# BMS_AFE_-_Thermistors.net
KiCad netlist of a schematic drawn in Altium Designer
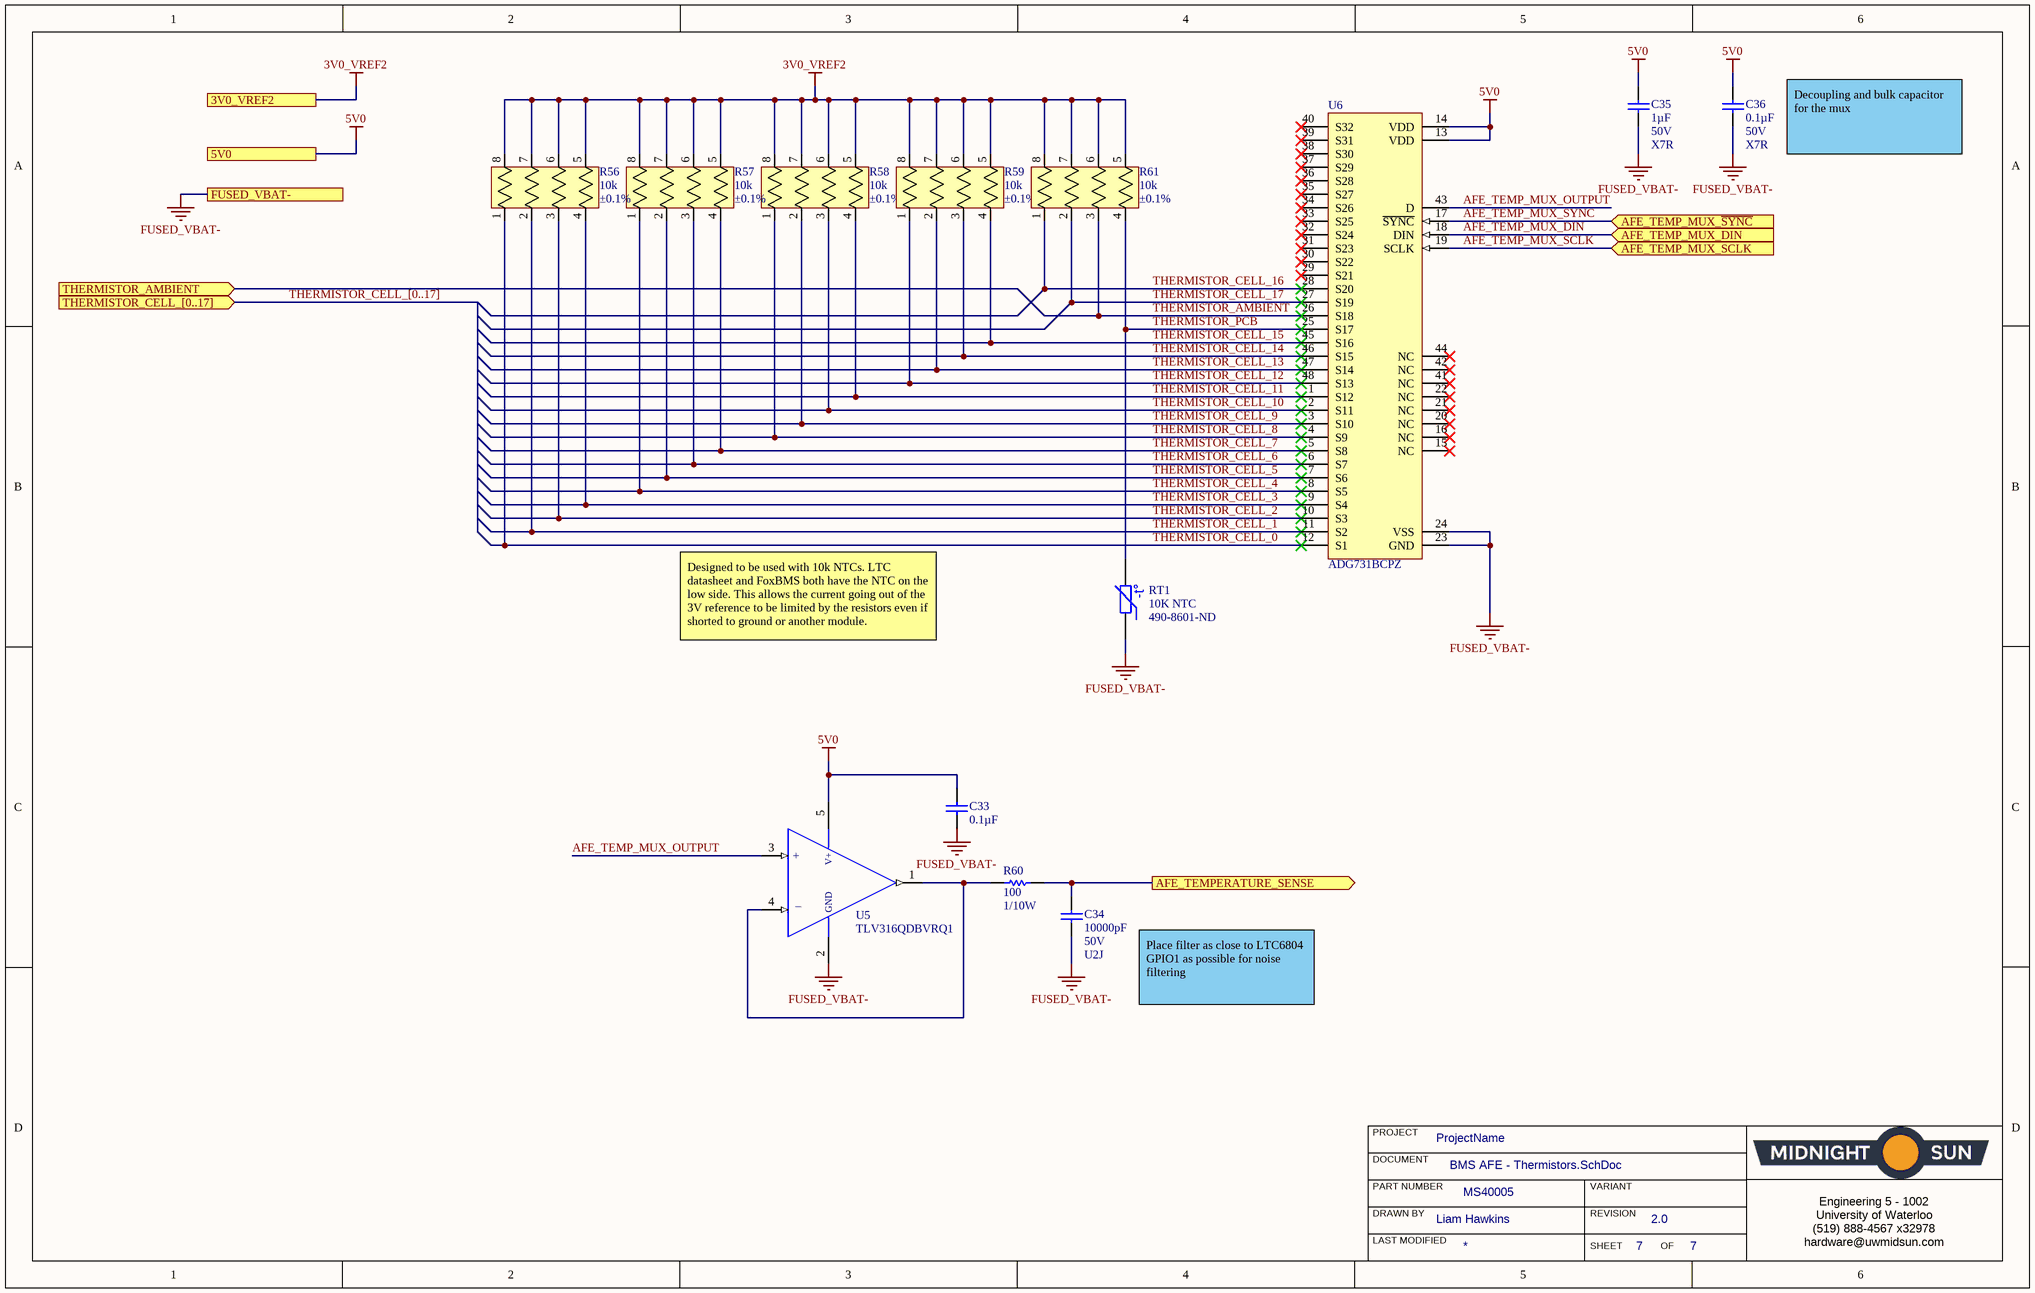
[diagram p0: BMS AFE - Thermistors.SchDoc]

(export (version "E")
  (design (tool "Eeschema 10.0.6"))
  (components
    (comp (ref "C33")
      (value "CAP CER 0.1UF 50V 10% X7R 0603")
      (footprint "CAP, 0603")
      (description "0.10µF ±10% 50V Ceramic Capacitor X7R 0603 (1608 Metric)")
      (fields
        (field (name "TOLERANCE") "±10%")
        (field (name "CAPACITANCE") "0.1µF")
        (field (name "VOLTAGE") "50V")
      )
      (libsource (lib "Schematic Diagrams") (part "CAP CER 0.1UF 50V 10% X7R 0603"))
    )
    (comp (ref "C34")
      (value "CAP CER 10nF 50V 5% X7R 0603")
      (footprint "CAP, 0603")
      (description "10000pF ±5% 50V Ceramic Capacitor U2J 0603 (1608 Metric)")
      (fields
        (field (name "TOLERANCE") "±5%")
        (field (name "CAPACITANCE") "10000pF")
        (field (name "VOLTAGE") "50V")
        (field (name "TEMPERATURE COEFFICIENT") "U2J")
      )
      (libsource (lib "Schematic Diagrams") (part "CAP CER 10nF 50V 5% X7R 0603"))
    )
    (comp (ref "C35")
      (value "CAP CER 1UF 50V 10% X7R 0603")
      (footprint "CAP, 0603")
      (description "1µF ±10% 50V Ceramic Capacitor X7R 0603 (1608 Metric)")
      (fields
        (field (name "TOLERANCE") "±10%")
        (field (name "CAPACITANCE") "1µF")
        (field (name "VOLTAGE") "50V")
        (field (name "TEMPERATURE COEFFICIENT") "X7R")
      )
      (libsource (lib "Schematic Diagrams") (part "CAP CER 1UF 50V 10% X7R 0603"))
    )
    (comp (ref "C36")
      (value "CAP CER 0.1UF 50V 10% X7R 0603")
      (footprint "CAP, 0603")
      (description "0.10µF ±10% 50V Ceramic Capacitor X7R 0603 (1608 Metric)")
      (fields
        (field (name "TOLERANCE") "±10%")
        (field (name "CAPACITANCE") "0.1µF")
        (field (name "VOLTAGE") "50V")
        (field (name "TEMPERATURE COEFFICIENT") "X7R")
      )
      (libsource (lib "Schematic Diagrams") (part "CAP CER 0.1UF 50V 10% X7R 0603"))
    )
    (comp (ref "R56")
      (value "RES ARRAY 10K OHM 0.1% 4RES 1206")
      (footprint "RES ARRAY 4RES 1206")
      (fields
        (field (name "MANUFACTURER") "Vishay Beyschlag")
        (field (name "MANUFACTURER PART NUMBER") "ACASA1002S1002P100")
        (field (name "RESISTANCE (OHMS)") "10k")
        (field (name "TOLERANCE") "±0.1%")
      )
      (libsource (lib "Schematic Diagrams") (part "RES ARRAY 10K OHM 0.1% 4RES 1206"))
    )
    (comp (ref "R57")
      (value "RES ARRAY 10K OHM 0.1% 4RES 1206")
      (footprint "RES ARRAY 4RES 1206")
      (fields
        (field (name "MANUFACTURER") "Vishay Beyschlag")
        (field (name "MANUFACTURER PART NUMBER") "ACASA1002S1002P100")
        (field (name "RESISTANCE (OHMS)") "10k")
        (field (name "TOLERANCE") "±0.1%")
      )
      (libsource (lib "Schematic Diagrams") (part "RES ARRAY 10K OHM 0.1% 4RES 1206"))
    )
    (comp (ref "R58")
      (value "RES ARRAY 10K OHM 0.1% 4RES 1206")
      (footprint "RES ARRAY 4RES 1206")
      (fields
        (field (name "MANUFACTURER") "Vishay Beyschlag")
        (field (name "MANUFACTURER PART NUMBER") "ACASA1002S1002P100")
        (field (name "RESISTANCE (OHMS)") "10k")
        (field (name "TOLERANCE") "±0.1%")
      )
      (libsource (lib "Schematic Diagrams") (part "RES ARRAY 10K OHM 0.1% 4RES 1206"))
    )
    (comp (ref "R59")
      (value "RES ARRAY 10K OHM 0.1% 4RES 1206")
      (footprint "RES ARRAY 4RES 1206")
      (fields
        (field (name "MANUFACTURER") "Vishay Beyschlag")
        (field (name "MANUFACTURER PART NUMBER") "ACASA1002S1002P100")
        (field (name "RESISTANCE (OHMS)") "10k")
        (field (name "TOLERANCE") "±0.1%")
      )
      (libsource (lib "Schematic Diagrams") (part "RES ARRAY 10K OHM 0.1% 4RES 1206"))
    )
    (comp (ref "R60")
      (value "RES 100 OHM 1% 1/10W 0603")
      (footprint "RES, 0603")
      (description "100 Ohm ±1% 0.1W, 1/10W Chip Resistor 0603 (1608 Metric) Moisture Resistant Thick Film")
      (fields
        (field (name "TOLERANCE") "±1%")
        (field (name "RESISTANCE") "100")
        (field (name "POWER") "1/10W")
      )
      (libsource (lib "Schematic Diagrams") (part "RES 100 OHM 1% 1/10W 0603"))
    )
    (comp (ref "R61")
      (value "RES ARRAY 10K OHM 0.1% 4RES 1206")
      (footprint "RES ARRAY 4RES 1206")
      (fields
        (field (name "MANUFACTURER") "Vishay Beyschlag")
        (field (name "MANUFACTURER PART NUMBER") "ACASA1002S1002P100")
        (field (name "RESISTANCE (OHMS)") "10k")
        (field (name "TOLERANCE") "±0.1%")
      )
      (libsource (lib "Schematic Diagrams") (part "RES ARRAY 10K OHM 0.1% 4RES 1206"))
    )
    (comp (ref "RT1")
      (value "10K NTC")
      (footprint "NTC THERMISTOR BEAD")
      (description "NTC Thermistor 10k Bead")
      (fields
        (field (name "MANUFACTURER") "Murata Electronics North America")
        (field (name "MANUFACTURER PART NUMBER") "NXRT15XH103FA1B030")
        (field (name "SUPPLIER PART NUMBER 1") "490-8601-ND")
      )
      (libsource (lib "Schematic Diagrams") (part "NTC THERMISTOR 10K 1% BEAD"))
    )
    (comp (ref "U5")
      (value "IC OP AMP GEN PURPOSE RR 10MHZ SOT-23-5")
      (footprint "IC OP AMP GP RR 10MHZ SOT-23-5")
      (description "General Purpose Amplifier 1 Circuit Rail-to-Rail SOT-23-5")
      (fields (field (name "MANUFACTURER PART NUMBER 1") "TLV316QDBVRQ1"))
      (libsource (lib "Schematic Diagrams") (part "IC OP AMP GEN PURPOSE RR 10MHZ SOT-23-5"))
    )
    (comp (ref "U6")
      (value "ADG731BCPZ")
      (footprint "TSQFP50P890X890X160-48M")
      (description "IC MULTIPLEXER 32X1 48LFCSP")
      (fields
        (field (name "MANUFACTURER") "Analog Devices Inc.")
        (field (name "MANUFACTURER PART NUMBER") "ADG731BSUZ")
      )
      (libsource (lib "Schematic Diagrams") (part "IC 32x1 Multiplexer ADG731BCPZ"))
    )
  )
  (nets
    (net (code "1") (name "/AFE_TEMPERATURE_SENSE") (class "Default")
      (node (ref "C34") (pin "1") (pinfunction "1_1") (pintype "passive"))
      (node (ref "R60") (pin "2") (pinfunction "2_2") (pintype "passive"))
    )
    (net (code "2") (name "/AFE_TEMP_MUX_DIN") (class "Default")
      (node (ref "U6") (pin "18") (pinfunction "DIN_18") (pintype "input"))
    )
    (net (code "3") (name "/AFE_TEMP_MUX_OUTPUT") (class "Default")
      (node (ref "U5") (pin "3") (pinfunction "+IN_3") (pintype "input"))
      (node (ref "U6") (pin "43") (pinfunction "D_43") (pintype "passive"))
    )
    (net (code "4") (name "/AFE_TEMP_MUX_SCLK") (class "Default")
      (node (ref "U6") (pin "19") (pinfunction "SCLK_19") (pintype "input"))
    )
    (net (code "5") (name "/AFE_TEMP_MUX_~{SYNC}") (class "Default")
      (node (ref "U6") (pin "17") (pinfunction "~{SYNC}_17") (pintype "input"))
    )
    (net (code "6") (name "/THERMISTOR_AMBIENT") (class "Default")
      (node (ref "R61") (pin "3") (pinfunction "3_3") (pintype "passive"))
      (node (ref "U6") (pin "26") (pinfunction "S18_26") (pintype "passive"))
    )
    (net (code "7") (name "/THERMISTOR_CELL_0") (class "Default")
      (node (ref "R56") (pin "1") (pinfunction "1_1") (pintype "passive"))
      (node (ref "U6") (pin "12") (pinfunction "S1_12") (pintype "passive"))
    )
    (net (code "8") (name "/THERMISTOR_CELL_1") (class "Default")
      (node (ref "R56") (pin "2") (pinfunction "2_2") (pintype "passive"))
      (node (ref "U6") (pin "11") (pinfunction "S2_11") (pintype "passive"))
    )
    (net (code "9") (name "/THERMISTOR_CELL_2") (class "Default")
      (node (ref "R56") (pin "3") (pinfunction "3_3") (pintype "passive"))
      (node (ref "U6") (pin "10") (pinfunction "S3_10") (pintype "passive"))
    )
    (net (code "10") (name "/THERMISTOR_CELL_3") (class "Default")
      (node (ref "R56") (pin "4") (pinfunction "4_4") (pintype "passive"))
      (node (ref "U6") (pin "9") (pinfunction "S4_9") (pintype "passive"))
    )
    (net (code "11") (name "/THERMISTOR_CELL_4") (class "Default")
      (node (ref "R57") (pin "1") (pinfunction "1_1") (pintype "passive"))
      (node (ref "U6") (pin "8") (pinfunction "S5_8") (pintype "passive"))
    )
    (net (code "12") (name "/THERMISTOR_CELL_5") (class "Default")
      (node (ref "R57") (pin "2") (pinfunction "2_2") (pintype "passive"))
      (node (ref "U6") (pin "7") (pinfunction "S6_7") (pintype "passive"))
    )
    (net (code "13") (name "/THERMISTOR_CELL_6") (class "Default")
      (node (ref "R57") (pin "3") (pinfunction "3_3") (pintype "passive"))
      (node (ref "U6") (pin "6") (pinfunction "S7_6") (pintype "passive"))
    )
    (net (code "14") (name "/THERMISTOR_CELL_7") (class "Default")
      (node (ref "R57") (pin "4") (pinfunction "4_4") (pintype "passive"))
      (node (ref "U6") (pin "5") (pinfunction "S8_5") (pintype "passive"))
    )
    (net (code "15") (name "/THERMISTOR_CELL_8") (class "Default")
      (node (ref "R58") (pin "1") (pinfunction "1_1") (pintype "passive"))
      (node (ref "U6") (pin "4") (pinfunction "S9_4") (pintype "passive"))
    )
    (net (code "16") (name "/THERMISTOR_CELL_9") (class "Default")
      (node (ref "R58") (pin "2") (pinfunction "2_2") (pintype "passive"))
      (node (ref "U6") (pin "3") (pinfunction "S10_3") (pintype "passive"))
    )
    (net (code "17") (name "/THERMISTOR_CELL_10") (class "Default")
      (node (ref "R58") (pin "3") (pinfunction "3_3") (pintype "passive"))
      (node (ref "U6") (pin "2") (pinfunction "S11_2") (pintype "passive"))
    )
    (net (code "18") (name "/THERMISTOR_CELL_11") (class "Default")
      (node (ref "R58") (pin "4") (pinfunction "4_4") (pintype "passive"))
      (node (ref "U6") (pin "1") (pinfunction "S12_1") (pintype "passive"))
    )
    (net (code "19") (name "/THERMISTOR_CELL_12") (class "Default")
      (node (ref "R59") (pin "1") (pinfunction "1_1") (pintype "passive"))
      (node (ref "U6") (pin "48") (pinfunction "S13_48") (pintype "passive"))
    )
    (net (code "20") (name "/THERMISTOR_CELL_13") (class "Default")
      (node (ref "R59") (pin "2") (pinfunction "2_2") (pintype "passive"))
      (node (ref "U6") (pin "47") (pinfunction "S14_47") (pintype "passive"))
    )
    (net (code "21") (name "/THERMISTOR_CELL_14") (class "Default")
      (node (ref "R59") (pin "3") (pinfunction "3_3") (pintype "passive"))
      (node (ref "U6") (pin "46") (pinfunction "S15_46") (pintype "passive"))
    )
    (net (code "22") (name "/THERMISTOR_CELL_15") (class "Default")
      (node (ref "R59") (pin "4") (pinfunction "4_4") (pintype "passive"))
      (node (ref "U6") (pin "45") (pinfunction "S16_45") (pintype "passive"))
    )
    (net (code "23") (name "/THERMISTOR_CELL_16") (class "Default")
      (node (ref "R61") (pin "1") (pinfunction "1_1") (pintype "passive"))
      (node (ref "U6") (pin "28") (pinfunction "S20_28") (pintype "passive"))
    )
    (net (code "24") (name "/THERMISTOR_CELL_17") (class "Default")
      (node (ref "R61") (pin "2") (pinfunction "2_2") (pintype "passive"))
      (node (ref "U6") (pin "27") (pinfunction "S19_27") (pintype "passive"))
    )
    (net (code "26") (name "/THERMISTOR_PCB") (class "Default")
      (node (ref "R61") (pin "4") (pinfunction "4_4") (pintype "passive"))
      (node (ref "RT1") (pin "2") (pinfunction "2_2") (pintype "passive"))
      (node (ref "U6") (pin "25") (pinfunction "S17_25") (pintype "passive"))
    )
    (net (code "27") (name "3V0_VREF2") (class "Default")
      (node (ref "R56") (pin "5") (pinfunction "5_5") (pintype "passive"))
      (node (ref "R56") (pin "6") (pinfunction "6_6") (pintype "passive"))
      (node (ref "R56") (pin "7") (pinfunction "7_7") (pintype "passive"))
      (node (ref "R56") (pin "8") (pinfunction "8_8") (pintype "passive"))
      (node (ref "R57") (pin "5") (pinfunction "5_5") (pintype "passive"))
      (node (ref "R57") (pin "6") (pinfunction "6_6") (pintype "passive"))
      (node (ref "R57") (pin "7") (pinfunction "7_7") (pintype "passive"))
      (node (ref "R57") (pin "8") (pinfunction "8_8") (pintype "passive"))
      (node (ref "R58") (pin "5") (pinfunction "5_5") (pintype "passive"))
      (node (ref "R58") (pin "6") (pinfunction "6_6") (pintype "passive"))
      (node (ref "R58") (pin "7") (pinfunction "7_7") (pintype "passive"))
      (node (ref "R58") (pin "8") (pinfunction "8_8") (pintype "passive"))
      (node (ref "R59") (pin "5") (pinfunction "5_5") (pintype "passive"))
      (node (ref "R59") (pin "6") (pinfunction "6_6") (pintype "passive"))
      (node (ref "R59") (pin "7") (pinfunction "7_7") (pintype "passive"))
      (node (ref "R59") (pin "8") (pinfunction "8_8") (pintype "passive"))
      (node (ref "R61") (pin "5") (pinfunction "5_5") (pintype "passive"))
      (node (ref "R61") (pin "6") (pinfunction "6_6") (pintype "passive"))
      (node (ref "R61") (pin "7") (pinfunction "7_7") (pintype "passive"))
      (node (ref "R61") (pin "8") (pinfunction "8_8") (pintype "passive"))
    )
    (net (code "28") (name "5V0") (class "Default")
      (node (ref "C33") (pin "1") (pinfunction "1_1") (pintype "passive"))
      (node (ref "C35") (pin "1") (pinfunction "1_1") (pintype "passive"))
      (node (ref "C36") (pin "1") (pinfunction "1_1") (pintype "passive"))
      (node (ref "U5") (pin "5") (pinfunction "VDD_5") (pintype "power_in"))
      (node (ref "U6") (pin "13") (pinfunction "VDD_13") (pintype "power_in"))
      (node (ref "U6") (pin "14") (pinfunction "VDD_14") (pintype "power_in"))
    )
    (net (code "29") (name "FUSED_VBAT-") (class "Default")
      (node (ref "C33") (pin "2") (pinfunction "2_2") (pintype "passive"))
      (node (ref "C34") (pin "2") (pinfunction "2_2") (pintype "passive"))
      (node (ref "C35") (pin "2") (pinfunction "2_2") (pintype "passive"))
      (node (ref "C36") (pin "2") (pinfunction "2_2") (pintype "passive"))
      (node (ref "RT1") (pin "1") (pinfunction "1_1") (pintype "passive"))
      (node (ref "U5") (pin "2") (pinfunction "VSS_2") (pintype "power_in"))
      (node (ref "U6") (pin "23") (pinfunction "GND_23") (pintype "power_in"))
      (node (ref "U6") (pin "24") (pinfunction "VSS_24") (pintype "power_in"))
    )
    (net (code "30") (name "Net-(U5--IN)") (class "Default")
      (node (ref "R60") (pin "1") (pinfunction "1_1") (pintype "passive"))
      (node (ref "U5") (pin "1") (pinfunction "OUTPUT_1") (pintype "output"))
      (node (ref "U5") (pin "4") (pinfunction "-IN_4") (pintype "input"))
    )
    (net (code "31") (name "unconnected-(U6-NC-Pad15)") (class "Default")
      (node (ref "U6") (pin "15") (pinfunction "NC_15") (pintype "passive+no_connect"))
    )
    (net (code "32") (name "unconnected-(U6-NC-Pad16)") (class "Default")
      (node (ref "U6") (pin "16") (pinfunction "NC_16") (pintype "passive+no_connect"))
    )
    (net (code "33") (name "unconnected-(U6-NC-Pad20)") (class "Default")
      (node (ref "U6") (pin "20") (pinfunction "NC_20") (pintype "passive+no_connect"))
    )
    (net (code "34") (name "unconnected-(U6-NC-Pad21)") (class "Default")
      (node (ref "U6") (pin "21") (pinfunction "NC_21") (pintype "passive+no_connect"))
    )
    (net (code "35") (name "unconnected-(U6-NC-Pad22)") (class "Default")
      (node (ref "U6") (pin "22") (pinfunction "NC_22") (pintype "passive+no_connect"))
    )
    (net (code "36") (name "unconnected-(U6-NC-Pad41)") (class "Default")
      (node (ref "U6") (pin "41") (pinfunction "NC_41") (pintype "passive+no_connect"))
    )
    (net (code "37") (name "unconnected-(U6-NC-Pad42)") (class "Default")
      (node (ref "U6") (pin "42") (pinfunction "NC_42") (pintype "passive+no_connect"))
    )
    (net (code "38") (name "unconnected-(U6-NC-Pad44)") (class "Default")
      (node (ref "U6") (pin "44") (pinfunction "NC_44") (pintype "passive+no_connect"))
    )
    (net (code "39") (name "unconnected-(U6-S21-Pad29)") (class "Default")
      (node (ref "U6") (pin "29") (pinfunction "S21_29") (pintype "passive+no_connect"))
    )
    (net (code "40") (name "unconnected-(U6-S22-Pad30)") (class "Default")
      (node (ref "U6") (pin "30") (pinfunction "S22_30") (pintype "passive+no_connect"))
    )
    (net (code "41") (name "unconnected-(U6-S23-Pad31)") (class "Default")
      (node (ref "U6") (pin "31") (pinfunction "S23_31") (pintype "passive+no_connect"))
    )
    (net (code "42") (name "unconnected-(U6-S24-Pad32)") (class "Default")
      (node (ref "U6") (pin "32") (pinfunction "S24_32") (pintype "passive+no_connect"))
    )
    (net (code "43") (name "unconnected-(U6-S25-Pad33)") (class "Default")
      (node (ref "U6") (pin "33") (pinfunction "S25_33") (pintype "passive+no_connect"))
    )
    (net (code "44") (name "unconnected-(U6-S26-Pad34)") (class "Default")
      (node (ref "U6") (pin "34") (pinfunction "S26_34") (pintype "passive+no_connect"))
    )
    (net (code "45") (name "unconnected-(U6-S27-Pad35)") (class "Default")
      (node (ref "U6") (pin "35") (pinfunction "S27_35") (pintype "passive+no_connect"))
    )
    (net (code "46") (name "unconnected-(U6-S28-Pad36)") (class "Default")
      (node (ref "U6") (pin "36") (pinfunction "S28_36") (pintype "passive+no_connect"))
    )
    (net (code "47") (name "unconnected-(U6-S29-Pad37)") (class "Default")
      (node (ref "U6") (pin "37") (pinfunction "S29_37") (pintype "passive+no_connect"))
    )
    (net (code "48") (name "unconnected-(U6-S30-Pad38)") (class "Default")
      (node (ref "U6") (pin "38") (pinfunction "S30_38") (pintype "passive+no_connect"))
    )
    (net (code "49") (name "unconnected-(U6-S31-Pad39)") (class "Default")
      (node (ref "U6") (pin "39") (pinfunction "S31_39") (pintype "passive+no_connect"))
    )
    (net (code "50") (name "unconnected-(U6-S32-Pad40)") (class "Default")
      (node (ref "U6") (pin "40") (pinfunction "S32_40") (pintype "passive+no_connect"))
    )
  )
)
